# LCD_BT.net
KiCad netlist of a schematic drawn in Altium Designer
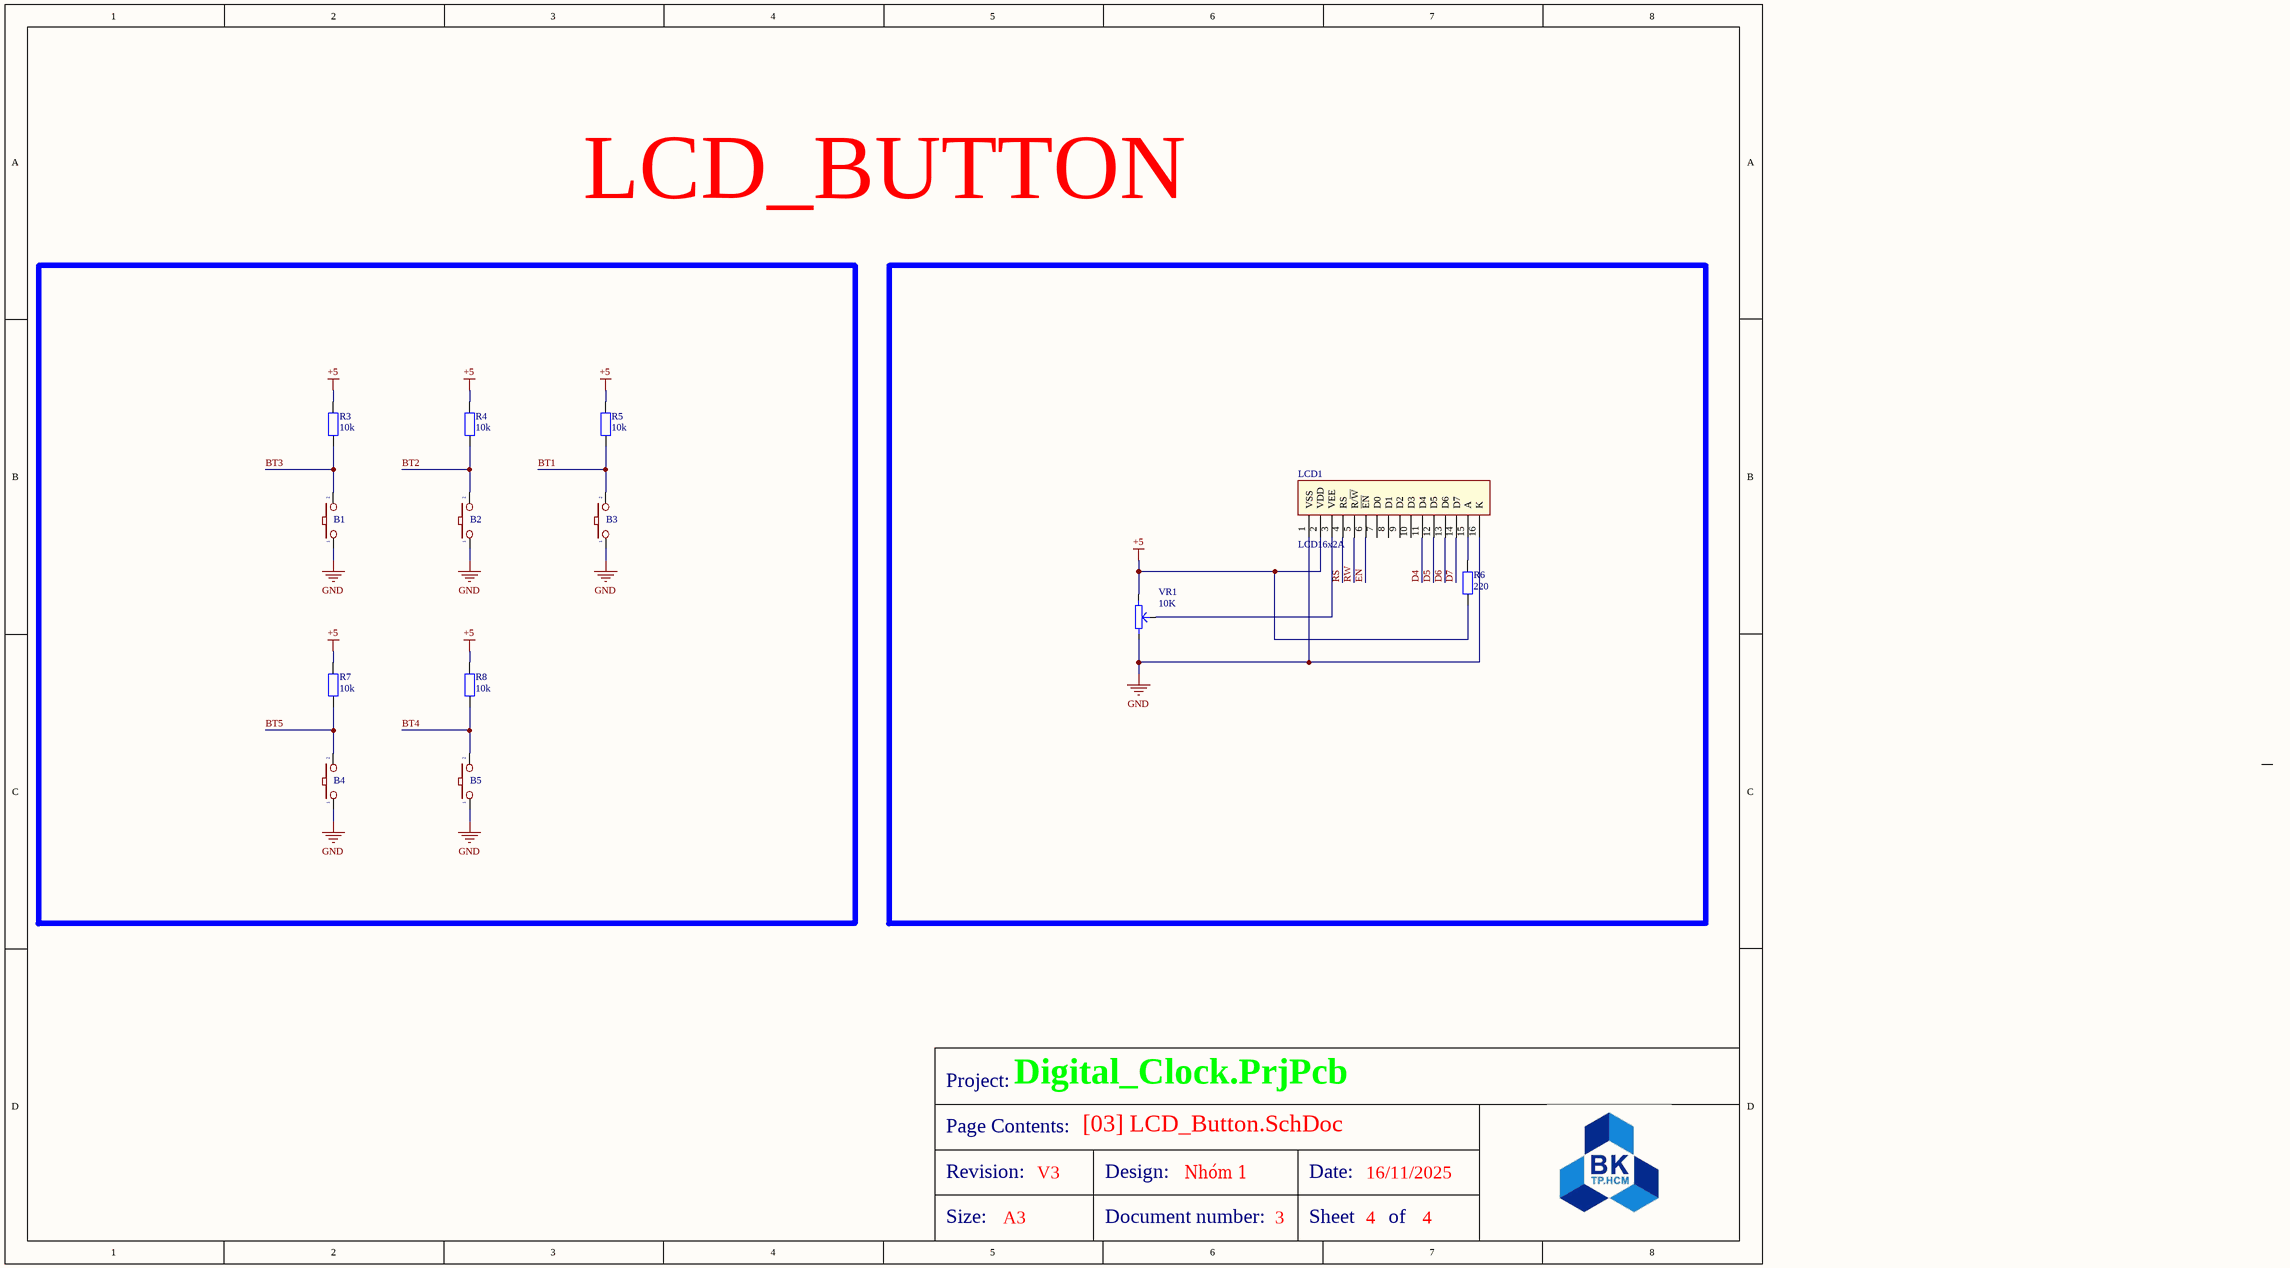
[diagram p0: LCD_BT.SchDoc]

(export (version "E")
  (design (tool "Eeschema 10.0.6"))
  (components
    (comp (ref "B1")
      (value "~")
      (footprint "SW2")
      (description "Switch button 2 pin")
      (libsource (lib "syhaunguyen") (part "SW2"))
    )
    (comp (ref "B2")
      (value "~")
      (footprint "SW2")
      (description "Switch button 2 pin")
      (libsource (lib "syhaunguyen") (part "SW2"))
    )
    (comp (ref "B3")
      (value "~")
      (footprint "SW2")
      (description "Switch button 2 pin")
      (libsource (lib "syhaunguyen") (part "SW2"))
    )
    (comp (ref "B4")
      (value "~")
      (footprint "SW2")
      (description "Switch button 2 pin")
      (libsource (lib "syhaunguyen") (part "SW2"))
    )
    (comp (ref "B5")
      (value "~")
      (footprint "SW2")
      (description "Switch button 2 pin")
      (libsource (lib "syhaunguyen") (part "SW2"))
    )
    (comp (ref "LCD1")
      (value "LCD16x2A")
      (footprint "LCD16X2")
      (description "LCD dipslay 16 char, 2 line")
      (libsource (lib "syhaunguyen") (part "LCD16x2"))
    )
    (comp (ref "R3")
      (value "10k")
      (footprint "R1/4W")
      (description "Resistor 1/4W")
      (libsource (lib "My Library") (part "R1/4W"))
    )
    (comp (ref "R4")
      (value "10k")
      (footprint "R1/4W")
      (description "Resistor 1/4W")
      (libsource (lib "My Library") (part "R1/4W"))
    )
    (comp (ref "R5")
      (value "10k")
      (footprint "R1/4W")
      (description "Resistor 1/4W")
      (libsource (lib "My Library") (part "R1/4W"))
    )
    (comp (ref "R6")
      (value "220")
      (footprint "R1/4W")
      (description "Resistor 1/4W")
      (libsource (lib "My Library") (part "R1/4W"))
    )
    (comp (ref "R7")
      (value "10k")
      (footprint "R1/4W")
      (description "Resistor 1/4W")
      (libsource (lib "My Library") (part "R1/4W"))
    )
    (comp (ref "R8")
      (value "10k")
      (footprint "R1/4W")
      (description "Resistor 1/4W")
      (libsource (lib "My Library") (part "R1/4W"))
    )
    (comp (ref "VR1")
      (value "10K")
      (footprint "Bien Tro Tam Giac Dung")
      (description "Cắm")
      (libsource (lib "Resistor") (part "Bien tro tam giac 10K Dung"))
    )
  )
  (nets
    (net (code "1") (name "+5") (class "Default")
      (node (ref "LCD1") (pin "2") (pinfunction "VDD_2") (pintype "passive"))
      (node (ref "R3") (pin "2") (pinfunction "2_2") (pintype "passive"))
      (node (ref "R4") (pin "2") (pinfunction "2_2") (pintype "passive"))
      (node (ref "R5") (pin "2") (pinfunction "2_2") (pintype "passive"))
      (node (ref "R6") (pin "1") (pinfunction "1_1") (pintype "passive"))
      (node (ref "R7") (pin "2") (pinfunction "2_2") (pintype "passive"))
      (node (ref "R8") (pin "2") (pinfunction "2_2") (pintype "passive"))
      (node (ref "VR1") (pin "1") (pinfunction "1_1") (pintype "passive"))
    )
    (net (code "2") (name "/BT1") (class "Default")
      (node (ref "B3") (pin "2") (pinfunction "2_2") (pintype "passive"))
      (node (ref "R5") (pin "1") (pinfunction "1_1") (pintype "passive"))
    )
    (net (code "3") (name "/BT2") (class "Default")
      (node (ref "B2") (pin "2") (pinfunction "2_2") (pintype "passive"))
      (node (ref "R4") (pin "1") (pinfunction "1_1") (pintype "passive"))
    )
    (net (code "4") (name "/BT3") (class "Default")
      (node (ref "B1") (pin "2") (pinfunction "2_2") (pintype "passive"))
      (node (ref "R3") (pin "1") (pinfunction "1_1") (pintype "passive"))
    )
    (net (code "5") (name "/BT4") (class "Default")
      (node (ref "B5") (pin "2") (pinfunction "2_2") (pintype "passive"))
      (node (ref "R8") (pin "1") (pinfunction "1_1") (pintype "passive"))
    )
    (net (code "6") (name "/BT5") (class "Default")
      (node (ref "B4") (pin "2") (pinfunction "2_2") (pintype "passive"))
      (node (ref "R7") (pin "1") (pinfunction "1_1") (pintype "passive"))
    )
    (net (code "7") (name "/D4") (class "Default")
      (node (ref "LCD1") (pin "11") (pinfunction "D4_11") (pintype "passive"))
    )
    (net (code "8") (name "/D5") (class "Default")
      (node (ref "LCD1") (pin "12") (pinfunction "D5_12") (pintype "passive"))
    )
    (net (code "9") (name "/D6") (class "Default")
      (node (ref "LCD1") (pin "13") (pinfunction "D6_13") (pintype "passive"))
    )
    (net (code "10") (name "/D7") (class "Default")
      (node (ref "LCD1") (pin "14") (pinfunction "D7_14") (pintype "passive"))
    )
    (net (code "11") (name "/EN") (class "Default")
      (node (ref "LCD1") (pin "6") (pinfunction "~{EN}_6") (pintype "passive"))
    )
    (net (code "12") (name "/RS") (class "Default")
      (node (ref "LCD1") (pin "4") (pinfunction "RS_4") (pintype "passive"))
    )
    (net (code "13") (name "/RW") (class "Default")
      (node (ref "LCD1") (pin "5") (pinfunction "R/~{W}_5") (pintype "passive"))
    )
    (net (code "14") (name "GND") (class "Default")
      (node (ref "B1") (pin "1") (pinfunction "1_1") (pintype "passive"))
      (node (ref "B2") (pin "1") (pinfunction "1_1") (pintype "passive"))
      (node (ref "B3") (pin "1") (pinfunction "1_1") (pintype "passive"))
      (node (ref "B4") (pin "1") (pinfunction "1_1") (pintype "passive"))
      (node (ref "B5") (pin "1") (pinfunction "1_1") (pintype "passive"))
      (node (ref "LCD1") (pin "1") (pinfunction "VSS_1") (pintype "passive"))
      (node (ref "LCD1") (pin "16") (pinfunction "K_16") (pintype "passive"))
      (node (ref "VR1") (pin "3") (pinfunction "3_3") (pintype "passive"))
    )
    (net (code "15") (name "Net-(LCD1-A)") (class "Default")
      (node (ref "LCD1") (pin "15") (pinfunction "A_15") (pintype "passive"))
      (node (ref "R6") (pin "2") (pinfunction "2_2") (pintype "passive"))
    )
    (net (code "16") (name "Net-(LCD1-VEE)") (class "Default")
      (node (ref "LCD1") (pin "3") (pinfunction "VEE_3") (pintype "passive"))
      (node (ref "VR1") (pin "2") (pinfunction "2_2") (pintype "passive"))
    )
    (net (code "17") (name "unconnected-(LCD1-D0-Pad7)") (class "Default")
      (node (ref "LCD1") (pin "7") (pinfunction "D0_7") (pintype "passive"))
    )
    (net (code "18") (name "unconnected-(LCD1-D1-Pad8)") (class "Default")
      (node (ref "LCD1") (pin "8") (pinfunction "D1_8") (pintype "passive"))
    )
    (net (code "19") (name "unconnected-(LCD1-D2-Pad9)") (class "Default")
      (node (ref "LCD1") (pin "9") (pinfunction "D2_9") (pintype "passive"))
    )
    (net (code "20") (name "unconnected-(LCD1-D3-Pad10)") (class "Default")
      (node (ref "LCD1") (pin "10") (pinfunction "D3_10") (pintype "passive"))
    )
  )
)
